# CANIO.net
KiCad netlist of a schematic drawn in EAGLE
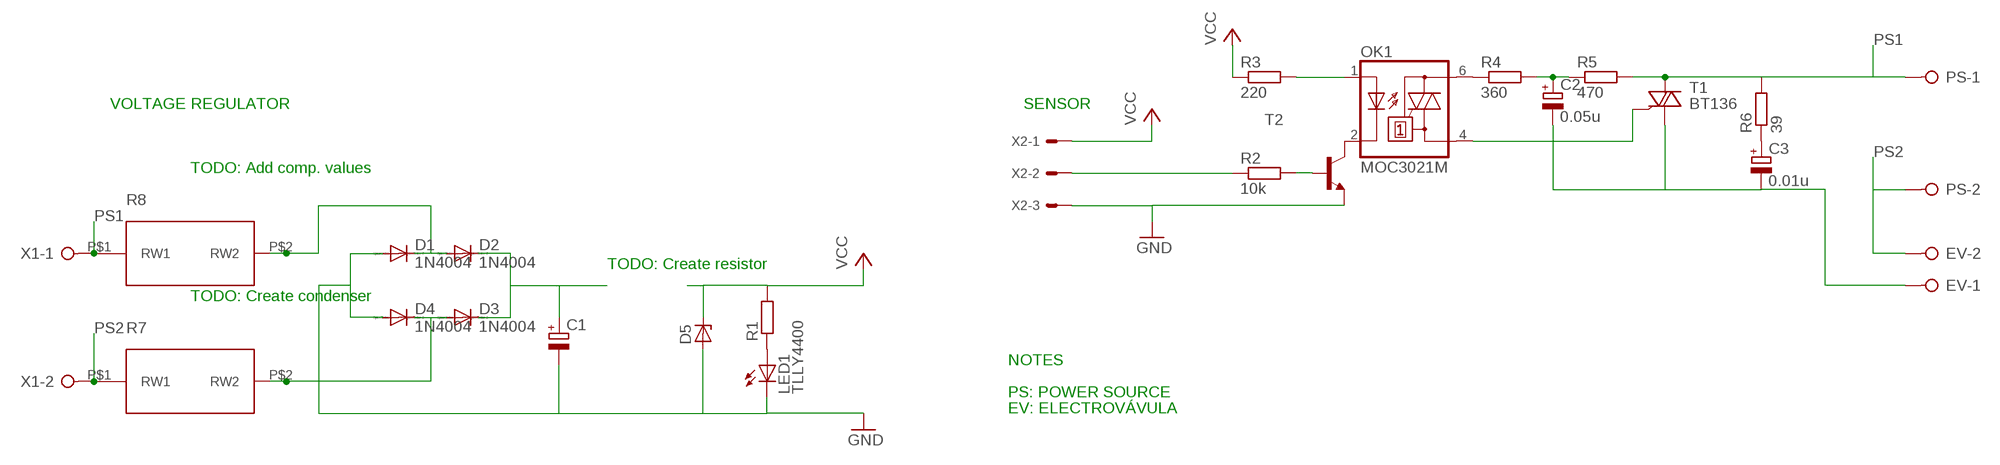
[diagram p0: schematic, sheet 1]

(export (version "E")
  (design (tool "Eeschema 10.0.6"))
  (components
    (comp (ref "C1")
      (value "CPOL-EUB45181A")
      (footprint "eagle-import:B45181A")
      (libsource (lib "eagle-import") (part "CPOL-EUB45181A"))
    )
    (comp (ref "C2")
      (value "0.05u")
      (footprint "eagle-import:B45181A")
      (libsource (lib "eagle-import") (part "CPOL-EUB45181A"))
    )
    (comp (ref "C3")
      (value "0.01u")
      (footprint "eagle-import:B45181A")
      (libsource (lib "eagle-import") (part "CPOL-EUB45181A"))
    )
    (comp (ref "D1")
      (value "1N4004")
      (footprint "eagle-import:DO41-10")
      (libsource (lib "eagle-import") (part "1N4004"))
    )
    (comp (ref "D2")
      (value "1N4004")
      (footprint "eagle-import:DO41-10")
      (libsource (lib "eagle-import") (part "1N4004"))
    )
    (comp (ref "D3")
      (value "1N4004")
      (footprint "eagle-import:DO41-10")
      (libsource (lib "eagle-import") (part "1N4004"))
    )
    (comp (ref "D4")
      (value "1N4004")
      (footprint "eagle-import:DO41-10")
      (libsource (lib "eagle-import") (part "1N4004"))
    )
    (comp (ref "D5")
      (value "ZENER-DIODEDO34-7")
      (footprint "eagle-import:DO34Z7")
      (libsource (lib "eagle-import") (part "ZENER-DIODEDO34-7"))
    )
    (comp (ref "EV")
      (value "W237-02P")
      (footprint "eagle-import:W237-132")
      (libsource (lib "eagle-import") (part "W237-02P"))
    )
    (comp (ref "LED1")
      (value "TLLY4400")
      (footprint "eagle-import:LED3MM")
      (fields (field (name "MF") "VISHAY SEMICONDUCTOR"))
      (libsource (lib "eagle-import") (part "TLLY4400"))
    )
    (comp (ref "OK1")
      (value "MOC3021M")
      (footprint "eagle-import:DIL06")
      (fields (field (name "MF") "FAIRCHILD SEMICONDUCTOR") (field (name "MPN") "MOC3021-M"))
      (libsource (lib "eagle-import") (part "MOC30M21"))
    )
    (comp (ref "PS")
      (value "W237-02P")
      (footprint "eagle-import:W237-132")
      (libsource (lib "eagle-import") (part "W237-02P"))
    )
    (comp (ref "R1")
      (value "R-EU_0204/5")
      (footprint "eagle-import:0204_5")
      (libsource (lib "eagle-import") (part "R-EU_0204/5"))
    )
    (comp (ref "R2")
      (value "10k")
      (footprint "eagle-import:0204_7")
      (libsource (lib "eagle-import") (part "resistor_348_R-EU_0204/7"))
    )
    (comp (ref "R3")
      (value "220")
      (footprint "eagle-import:0204_7")
      (libsource (lib "eagle-import") (part "resistor_348_R-EU_0204/7"))
    )
    (comp (ref "R4")
      (value "360")
      (footprint "eagle-import:0204_7")
      (libsource (lib "eagle-import") (part "R-EU_0204/7"))
    )
    (comp (ref "R5")
      (value "470")
      (footprint "eagle-import:0204_7")
      (libsource (lib "eagle-import") (part "R-EU_0204/7"))
    )
    (comp (ref "R6")
      (value "39")
      (footprint "eagle-import:0204_7")
      (libsource (lib "eagle-import") (part "R-EU_0204/7"))
    )
    (comp (ref "R7")
      (value "RESISTOR1W")
      (footprint "eagle-import:RESISTOR1W")
      (libsource (lib "eagle-import") (part "RESISTOR1W"))
    )
    (comp (ref "R8")
      (value "RESISTOR1W")
      (footprint "eagle-import:RESISTOR1W")
      (libsource (lib "eagle-import") (part "RESISTOR1W"))
    )
    (comp (ref "T1")
      (value "BT136")
      (footprint "eagle-import:TO220AB")
      (libsource (lib "eagle-import") (part "BT136"))
    )
    (comp (ref "T2")
      (value "-NPN-TO92")
      (footprint "eagle-import:TO92")
      (libsource (lib "eagle-import") (part "-NPN-TO92"))
    )
    (comp (ref "X1")
      (value "W237-02P")
      (footprint "eagle-import:W237-132")
      (libsource (lib "eagle-import") (part "W237-02P"))
    )
    (comp (ref "X2")
      (value "KK-156-3")
      (footprint "eagle-import:KK-156-3")
      (libsource (lib "eagle-import") (part "KK-156-3"))
    )
  )
  (nets
    (net (code "1") (name "/PS1") (class "Default")
      (node (ref "PS") (pin "1") (pinfunction "KL_1") (pintype "passive"))
      (node (ref "R5") (pin "2") (pinfunction "2_2") (pintype "passive"))
      (node (ref "R6") (pin "2") (pinfunction "2_2") (pintype "passive"))
      (node (ref "R8") (pin "P$1") (pinfunction "RW1_P$1") (pintype "bidirectional"))
      (node (ref "T1") (pin "2") (pinfunction "A2_2") (pintype "passive"))
      (node (ref "X1") (pin "1") (pinfunction "KL_1") (pintype "passive"))
    )
    (net (code "2") (name "/PS2") (class "Default")
      (node (ref "EV") (pin "2") (pinfunction "KL_2") (pintype "passive"))
      (node (ref "PS") (pin "2") (pinfunction "KL_2") (pintype "passive"))
      (node (ref "R7") (pin "P$1") (pinfunction "RW1_P$1") (pintype "bidirectional"))
      (node (ref "X1") (pin "2") (pinfunction "KL_2") (pintype "passive"))
    )
    (net (code "3") (name "GND") (class "Default")
      (node (ref "C1") (pin "-") (pinfunction "-_-") (pintype "passive"))
      (node (ref "D1") (pin "A") (pinfunction "A_A") (pintype "passive"))
      (node (ref "D4") (pin "A") (pinfunction "A_A") (pintype "passive"))
      (node (ref "D5") (pin "A") (pinfunction "A_A") (pintype "passive"))
      (node (ref "LED1") (pin "K") (pinfunction "C_K") (pintype "passive"))
      (node (ref "T2") (pin "1") (pinfunction "E_1") (pintype "passive"))
      (node (ref "X2") (pin "3") (pinfunction "S_3") (pintype "passive"))
    )
    (net (code "4") (name "Net-(C1-Pad+)") (class "Default")
      (node (ref "C1") (pin "+") (pinfunction "+_+") (pintype "passive"))
      (node (ref "D2") (pin "C") (pinfunction "C_C") (pintype "passive"))
      (node (ref "D3") (pin "C") (pinfunction "C_C") (pintype "passive"))
    )
    (net (code "5") (name "Net-(C2-Pad+)") (class "Default")
      (node (ref "C2") (pin "+") (pinfunction "+_+") (pintype "passive"))
      (node (ref "R4") (pin "2") (pinfunction "2_2") (pintype "passive"))
      (node (ref "R5") (pin "1") (pinfunction "1_1") (pintype "passive"))
    )
    (net (code "6") (name "Net-(C3-Pad+)") (class "Default")
      (node (ref "C3") (pin "+") (pinfunction "+_+") (pintype "passive"))
      (node (ref "R6") (pin "1") (pinfunction "1_1") (pintype "passive"))
    )
    (net (code "7") (name "Net-(EVA-KL)") (class "Default")
      (node (ref "C2") (pin "-") (pinfunction "-_-") (pintype "passive"))
      (node (ref "C3") (pin "-") (pinfunction "-_-") (pintype "passive"))
      (node (ref "EV") (pin "1") (pinfunction "KL_1") (pintype "passive"))
      (node (ref "T1") (pin "1") (pinfunction "A1_1") (pintype "passive"))
    )
    (net (code "8") (name "Net-(LED1-PadA)") (class "Default")
      (node (ref "LED1") (pin "A") (pinfunction "A_A") (pintype "passive"))
      (node (ref "R1") (pin "1") (pinfunction "1_1") (pintype "passive"))
    )
    (net (code "9") (name "Net-(OK1-A)") (class "Default")
      (node (ref "OK1") (pin "1") (pinfunction "A_1") (pintype "passive"))
      (node (ref "R3") (pin "2") (pinfunction "2_2") (pintype "passive"))
    )
    (net (code "10") (name "Net-(OK1-A1)") (class "Default")
      (node (ref "OK1") (pin "4") (pinfunction "A1_4") (pintype "passive"))
      (node (ref "T1") (pin "3") (pinfunction "G_3") (pintype "passive"))
    )
    (net (code "11") (name "Net-(OK1-A2)") (class "Default")
      (node (ref "OK1") (pin "6") (pinfunction "A2_6") (pintype "passive"))
      (node (ref "R4") (pin "1") (pinfunction "1_1") (pintype "passive"))
    )
    (net (code "12") (name "Net-(OK1-C)") (class "Default")
      (node (ref "OK1") (pin "2") (pinfunction "C_2") (pintype "passive"))
      (node (ref "T2") (pin "3") (pinfunction "C_3") (pintype "passive"))
    )
    (net (code "13") (name "Net-(R7-RW2)") (class "Default")
      (node (ref "D3") (pin "A") (pinfunction "A_A") (pintype "passive"))
      (node (ref "D4") (pin "C") (pinfunction "C_C") (pintype "passive"))
      (node (ref "R7") (pin "P$2") (pinfunction "RW2_P$2") (pintype "bidirectional"))
    )
    (net (code "14") (name "Net-(R8-RW2)") (class "Default")
      (node (ref "D1") (pin "C") (pinfunction "C_C") (pintype "passive"))
      (node (ref "D2") (pin "A") (pinfunction "A_A") (pintype "passive"))
      (node (ref "R8") (pin "P$2") (pinfunction "RW2_P$2") (pintype "bidirectional"))
    )
    (net (code "15") (name "Net-(T2-B)") (class "Default")
      (node (ref "R2") (pin "2") (pinfunction "2_2") (pintype "passive"))
      (node (ref "T2") (pin "2") (pinfunction "B_2") (pintype "passive"))
    )
    (net (code "16") (name "Net-(X2B-S)") (class "Default")
      (node (ref "R2") (pin "1") (pinfunction "1_1") (pintype "passive"))
      (node (ref "X2") (pin "2") (pinfunction "S_2") (pintype "passive"))
    )
    (net (code "17") (name "VCC") (class "Default")
      (node (ref "D5") (pin "C") (pinfunction "C_C") (pintype "passive"))
      (node (ref "R1") (pin "2") (pinfunction "2_2") (pintype "passive"))
      (node (ref "R3") (pin "1") (pinfunction "1_1") (pintype "passive"))
      (node (ref "X2") (pin "1") (pinfunction "S_1") (pintype "passive"))
    )
  )
)
